# v5-IRarray.net
KiCad netlist of a schematic drawn in Altium Designer
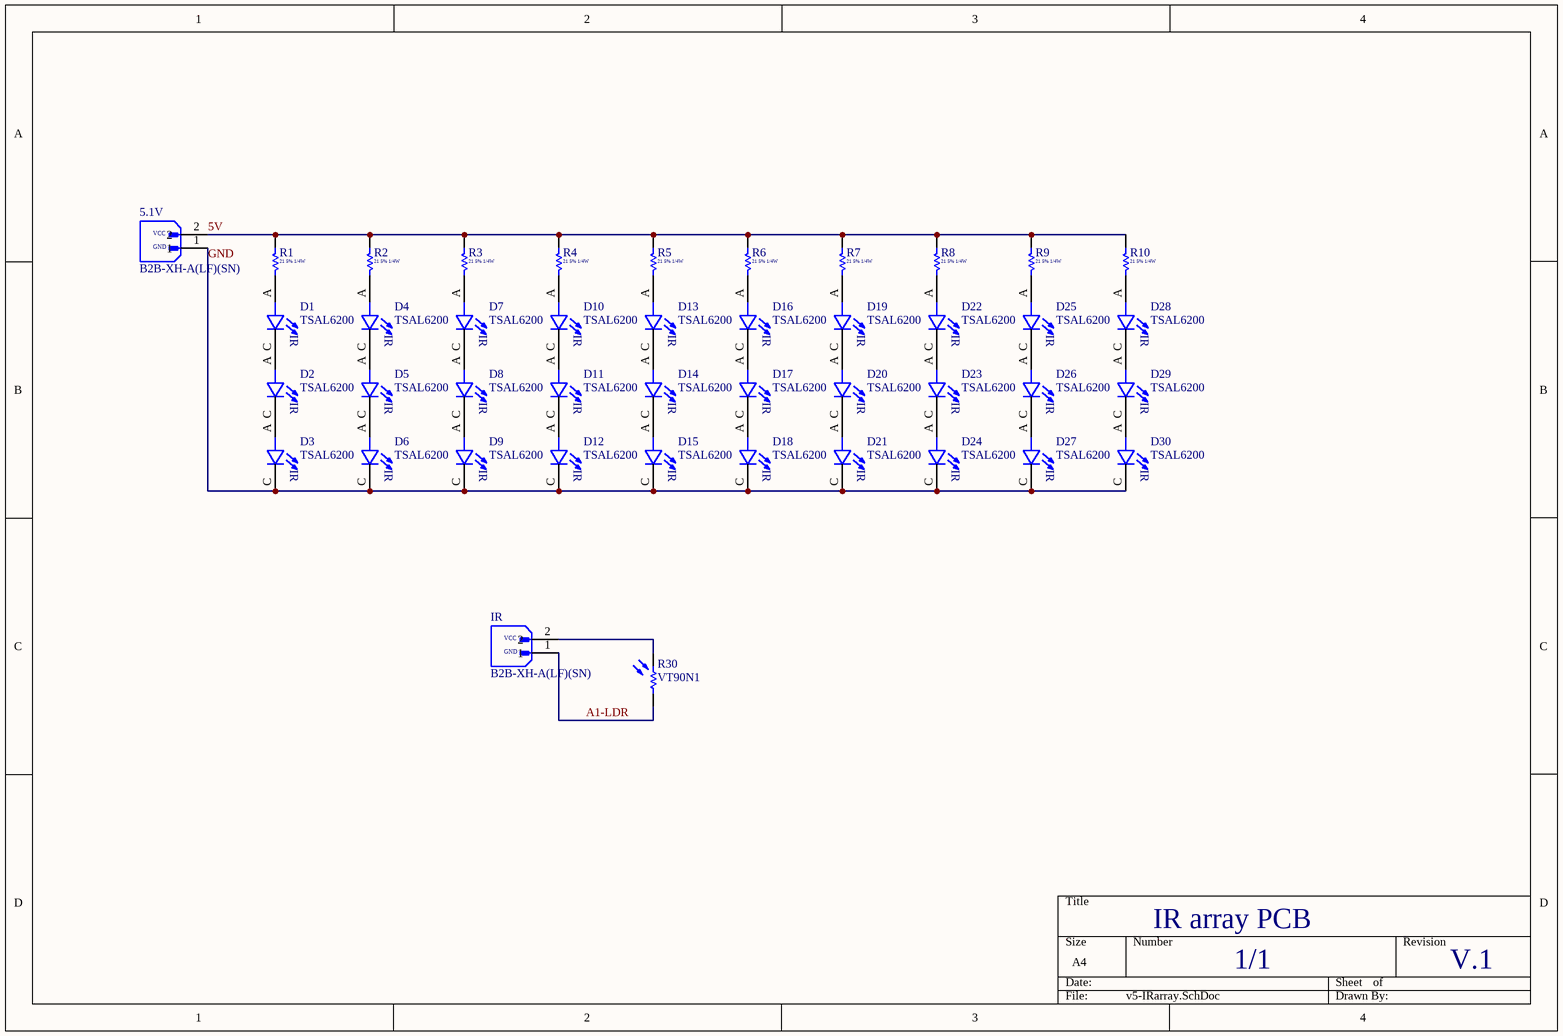
[diagram p0: v5-IRarray.SchDoc]

(export (version "E")
  (design (tool "Eeschema 10.0.6"))
  (components
    (comp (ref "5.1V")
      (value "B2B-XH-A(LF)(SN)")
      (footprint "JST_B2B-XH-A(LF)(SN)")
      (description "Connector Header Through Hole 2 position 0.098 (2.50mm)")
      (fields (field (name "MF") "JST Sales America Inc."))
      (libsource (lib "B2B-XH-A(LF)(SN)") (part "B2B-XH-A(LF)(SN)"))
    )
    (comp (ref "D1")
      (value "TSAL6200")
      (footprint "SFH45547")
      (libsource (lib "IRarrayPCB") (part "SFH4547"))
    )
    (comp (ref "D2")
      (value "TSAL6200")
      (footprint "SFH45547")
      (libsource (lib "IRarrayPCB") (part "SFH4547"))
    )
    (comp (ref "D3")
      (value "TSAL6200")
      (footprint "SFH45547")
      (libsource (lib "IRarrayPCB") (part "SFH4547"))
    )
    (comp (ref "D4")
      (value "TSAL6200")
      (footprint "SFH45547")
      (libsource (lib "IRarrayPCB") (part "SFH4547"))
    )
    (comp (ref "D5")
      (value "TSAL6200")
      (footprint "SFH45547")
      (libsource (lib "IRarrayPCB") (part "SFH4547"))
    )
    (comp (ref "D6")
      (value "TSAL6200")
      (footprint "SFH45547")
      (libsource (lib "IRarrayPCB") (part "SFH4547"))
    )
    (comp (ref "D7")
      (value "TSAL6200")
      (footprint "SFH45547")
      (libsource (lib "IRarrayPCB") (part "SFH4547"))
    )
    (comp (ref "D8")
      (value "TSAL6200")
      (footprint "SFH45547")
      (libsource (lib "IRarrayPCB") (part "SFH4547"))
    )
    (comp (ref "D9")
      (value "TSAL6200")
      (footprint "SFH45547")
      (libsource (lib "IRarrayPCB") (part "SFH4547"))
    )
    (comp (ref "D10")
      (value "TSAL6200")
      (footprint "SFH45547")
      (libsource (lib "IRarrayPCB") (part "SFH4547"))
    )
    (comp (ref "D11")
      (value "TSAL6200")
      (footprint "SFH45547")
      (libsource (lib "IRarrayPCB") (part "SFH4547"))
    )
    (comp (ref "D12")
      (value "TSAL6200")
      (footprint "SFH45547")
      (libsource (lib "IRarrayPCB") (part "SFH4547"))
    )
    (comp (ref "D13")
      (value "TSAL6200")
      (footprint "SFH45547")
      (libsource (lib "IRarrayPCB") (part "SFH4547"))
    )
    (comp (ref "D14")
      (value "TSAL6200")
      (footprint "SFH45547")
      (libsource (lib "IRarrayPCB") (part "SFH4547"))
    )
    (comp (ref "D15")
      (value "TSAL6200")
      (footprint "SFH45547")
      (libsource (lib "IRarrayPCB") (part "SFH4547"))
    )
    (comp (ref "D16")
      (value "TSAL6200")
      (footprint "SFH45547")
      (libsource (lib "IRarrayPCB") (part "SFH4547"))
    )
    (comp (ref "D17")
      (value "TSAL6200")
      (footprint "SFH45547")
      (libsource (lib "IRarrayPCB") (part "SFH4547"))
    )
    (comp (ref "D18")
      (value "TSAL6200")
      (footprint "SFH45547")
      (libsource (lib "IRarrayPCB") (part "SFH4547"))
    )
    (comp (ref "D19")
      (value "TSAL6200")
      (footprint "SFH45547")
      (libsource (lib "IRarrayPCB") (part "SFH4547"))
    )
    (comp (ref "D20")
      (value "TSAL6200")
      (footprint "SFH45547")
      (libsource (lib "IRarrayPCB") (part "SFH4547"))
    )
    (comp (ref "D21")
      (value "TSAL6200")
      (footprint "SFH45547")
      (libsource (lib "IRarrayPCB") (part "SFH4547"))
    )
    (comp (ref "D22")
      (value "TSAL6200")
      (footprint "SFH45547")
      (libsource (lib "IRarrayPCB") (part "SFH4547"))
    )
    (comp (ref "D23")
      (value "TSAL6200")
      (footprint "SFH45547")
      (libsource (lib "IRarrayPCB") (part "SFH4547"))
    )
    (comp (ref "D24")
      (value "TSAL6200")
      (footprint "SFH45547")
      (libsource (lib "IRarrayPCB") (part "SFH4547"))
    )
    (comp (ref "D25")
      (value "TSAL6200")
      (footprint "SFH45547")
      (libsource (lib "IRarrayPCB") (part "SFH4547"))
    )
    (comp (ref "D26")
      (value "TSAL6200")
      (footprint "SFH45547")
      (libsource (lib "IRarrayPCB") (part "SFH4547"))
    )
    (comp (ref "D27")
      (value "TSAL6200")
      (footprint "SFH45547")
      (libsource (lib "IRarrayPCB") (part "SFH4547"))
    )
    (comp (ref "D28")
      (value "TSAL6200")
      (footprint "SFH45547")
      (libsource (lib "IRarrayPCB") (part "SFH4547"))
    )
    (comp (ref "D29")
      (value "TSAL6200")
      (footprint "SFH45547")
      (libsource (lib "IRarrayPCB") (part "SFH4547"))
    )
    (comp (ref "D30")
      (value "TSAL6200")
      (footprint "SFH45547")
      (libsource (lib "IRarrayPCB") (part "SFH4547"))
    )
    (comp (ref "IR")
      (value "B2B-XH-A(LF)(SN)")
      (footprint "JST_B2B-XH-A(LF)(SN)")
      (description "Connector Header Through Hole 2 position 0.098 (2.50mm)")
      (fields (field (name "MF") "JST Sales America Inc."))
      (libsource (lib "B2B-XH-A(LF)(SN)") (part "B2B-XH-A(LF)(SN)"))
    )
    (comp (ref "R1")
      (value "21 5% 1/4W")
      (footprint "R1206")
      (description "SMD 1206 0.25W 5% 200V")
      (libsource (lib "MyLib1") (part "R-1206"))
    )
    (comp (ref "R2")
      (value "21 5% 1/4W")
      (footprint "R1206")
      (description "SMD 1206 0.25W 5% 200V")
      (libsource (lib "MyLib1") (part "R-1206"))
    )
    (comp (ref "R3")
      (value "21 5% 1/4W")
      (footprint "R1206")
      (description "SMD 1206 0.25W 5% 200V")
      (libsource (lib "MyLib1") (part "R-1206"))
    )
    (comp (ref "R4")
      (value "21 5% 1/4W")
      (footprint "R1206")
      (description "SMD 1206 0.25W 5% 200V")
      (libsource (lib "MyLib1") (part "R-1206"))
    )
    (comp (ref "R5")
      (value "21 5% 1/4W")
      (footprint "R1206")
      (description "SMD 1206 0.25W 5% 200V")
      (libsource (lib "MyLib1") (part "R-1206"))
    )
    (comp (ref "R6")
      (value "21 5% 1/4W")
      (footprint "R1206")
      (description "SMD 1206 0.25W 5% 200V")
      (libsource (lib "MyLib1") (part "R-1206"))
    )
    (comp (ref "R7")
      (value "21 5% 1/4W")
      (footprint "R1206")
      (description "SMD 1206 0.25W 5% 200V")
      (libsource (lib "MyLib1") (part "R-1206"))
    )
    (comp (ref "R8")
      (value "21 5% 1/4W")
      (footprint "R1206")
      (description "SMD 1206 0.25W 5% 200V")
      (libsource (lib "MyLib1") (part "R-1206"))
    )
    (comp (ref "R9")
      (value "21 5% 1/4W")
      (footprint "R1206")
      (description "SMD 1206 0.25W 5% 200V")
      (libsource (lib "MyLib1") (part "R-1206"))
    )
    (comp (ref "R10")
      (value "21 5% 1/4W")
      (footprint "R1206")
      (description "SMD 1206 0.25W 5% 200V")
      (libsource (lib "MyLib1") (part "R-1206"))
    )
    (comp (ref "R30")
      (value "VT90N1")
      (footprint "EXCE-VT90N1")
      (description "Photoconductive Resistor, 200 kOhm, 100 V, 80 mW, -40 to 75 degC, 2-Pin THD, RoHS")
      (fields (field (name "MANUFACTURER") "Excelitas Technology"))
      (libsource (lib "Altium Content Vault") (part "PHOTO-RES-2"))
    )
  )
  (nets
    (net (code "1") (name "/5V") (class "Default")
      (node (ref "5.1V") (pin "2") (pinfunction "2_2") (pintype "passive"))
      (node (ref "R1") (pin "1") (pinfunction "1_1") (pintype "passive"))
      (node (ref "R10") (pin "1") (pinfunction "1_1") (pintype "passive"))
      (node (ref "R2") (pin "1") (pinfunction "1_1") (pintype "passive"))
      (node (ref "R3") (pin "1") (pinfunction "1_1") (pintype "passive"))
      (node (ref "R4") (pin "1") (pinfunction "1_1") (pintype "passive"))
      (node (ref "R5") (pin "1") (pinfunction "1_1") (pintype "passive"))
      (node (ref "R6") (pin "1") (pinfunction "1_1") (pintype "passive"))
      (node (ref "R7") (pin "1") (pinfunction "1_1") (pintype "passive"))
      (node (ref "R8") (pin "1") (pinfunction "1_1") (pintype "passive"))
      (node (ref "R9") (pin "1") (pinfunction "1_1") (pintype "passive"))
    )
    (net (code "2") (name "/A1-LDR") (class "Default")
      (node (ref "IR") (pin "1") (pinfunction "1_1") (pintype "passive"))
      (node (ref "R30") (pin "1") (pinfunction "1_1") (pintype "passive"))
    )
    (net (code "3") (name "/GND") (class "Default")
      (node (ref "5.1V") (pin "1") (pinfunction "1_1") (pintype "passive"))
      (node (ref "D12") (pin "C") (pinfunction "C_C") (pintype "passive"))
      (node (ref "D15") (pin "C") (pinfunction "C_C") (pintype "passive"))
      (node (ref "D18") (pin "C") (pinfunction "C_C") (pintype "passive"))
      (node (ref "D21") (pin "C") (pinfunction "C_C") (pintype "passive"))
      (node (ref "D24") (pin "C") (pinfunction "C_C") (pintype "passive"))
      (node (ref "D27") (pin "C") (pinfunction "C_C") (pintype "passive"))
      (node (ref "D3") (pin "C") (pinfunction "C_C") (pintype "passive"))
      (node (ref "D30") (pin "C") (pinfunction "C_C") (pintype "passive"))
      (node (ref "D6") (pin "C") (pinfunction "C_C") (pintype "passive"))
      (node (ref "D9") (pin "C") (pinfunction "C_C") (pintype "passive"))
    )
    (net (code "4") (name "Net-(D1-PadA)") (class "Default")
      (node (ref "D1") (pin "A") (pinfunction "A_A") (pintype "passive"))
      (node (ref "R1") (pin "2") (pinfunction "2_2") (pintype "passive"))
    )
    (net (code "5") (name "Net-(D1-PadC)") (class "Default")
      (node (ref "D1") (pin "C") (pinfunction "C_C") (pintype "passive"))
      (node (ref "D2") (pin "A") (pinfunction "A_A") (pintype "passive"))
    )
    (net (code "6") (name "Net-(D2-PadC)") (class "Default")
      (node (ref "D2") (pin "C") (pinfunction "C_C") (pintype "passive"))
      (node (ref "D3") (pin "A") (pinfunction "A_A") (pintype "passive"))
    )
    (net (code "7") (name "Net-(D4-PadA)") (class "Default")
      (node (ref "D4") (pin "A") (pinfunction "A_A") (pintype "passive"))
      (node (ref "R2") (pin "2") (pinfunction "2_2") (pintype "passive"))
    )
    (net (code "8") (name "Net-(D4-PadC)") (class "Default")
      (node (ref "D4") (pin "C") (pinfunction "C_C") (pintype "passive"))
      (node (ref "D5") (pin "A") (pinfunction "A_A") (pintype "passive"))
    )
    (net (code "9") (name "Net-(D5-PadC)") (class "Default")
      (node (ref "D5") (pin "C") (pinfunction "C_C") (pintype "passive"))
      (node (ref "D6") (pin "A") (pinfunction "A_A") (pintype "passive"))
    )
    (net (code "10") (name "Net-(D7-PadA)") (class "Default")
      (node (ref "D7") (pin "A") (pinfunction "A_A") (pintype "passive"))
      (node (ref "R3") (pin "2") (pinfunction "2_2") (pintype "passive"))
    )
    (net (code "11") (name "Net-(D7-PadC)") (class "Default")
      (node (ref "D7") (pin "C") (pinfunction "C_C") (pintype "passive"))
      (node (ref "D8") (pin "A") (pinfunction "A_A") (pintype "passive"))
    )
    (net (code "12") (name "Net-(D8-PadC)") (class "Default")
      (node (ref "D8") (pin "C") (pinfunction "C_C") (pintype "passive"))
      (node (ref "D9") (pin "A") (pinfunction "A_A") (pintype "passive"))
    )
    (net (code "13") (name "Net-(D10-PadA)") (class "Default")
      (node (ref "D10") (pin "A") (pinfunction "A_A") (pintype "passive"))
      (node (ref "R4") (pin "2") (pinfunction "2_2") (pintype "passive"))
    )
    (net (code "14") (name "Net-(D10-PadC)") (class "Default")
      (node (ref "D10") (pin "C") (pinfunction "C_C") (pintype "passive"))
      (node (ref "D11") (pin "A") (pinfunction "A_A") (pintype "passive"))
    )
    (net (code "15") (name "Net-(D11-PadC)") (class "Default")
      (node (ref "D11") (pin "C") (pinfunction "C_C") (pintype "passive"))
      (node (ref "D12") (pin "A") (pinfunction "A_A") (pintype "passive"))
    )
    (net (code "16") (name "Net-(D13-PadA)") (class "Default")
      (node (ref "D13") (pin "A") (pinfunction "A_A") (pintype "passive"))
      (node (ref "R5") (pin "2") (pinfunction "2_2") (pintype "passive"))
    )
    (net (code "17") (name "Net-(D13-PadC)") (class "Default")
      (node (ref "D13") (pin "C") (pinfunction "C_C") (pintype "passive"))
      (node (ref "D14") (pin "A") (pinfunction "A_A") (pintype "passive"))
    )
    (net (code "18") (name "Net-(D14-PadC)") (class "Default")
      (node (ref "D14") (pin "C") (pinfunction "C_C") (pintype "passive"))
      (node (ref "D15") (pin "A") (pinfunction "A_A") (pintype "passive"))
    )
    (net (code "19") (name "Net-(D16-PadA)") (class "Default")
      (node (ref "D16") (pin "A") (pinfunction "A_A") (pintype "passive"))
      (node (ref "R6") (pin "2") (pinfunction "2_2") (pintype "passive"))
    )
    (net (code "20") (name "Net-(D16-PadC)") (class "Default")
      (node (ref "D16") (pin "C") (pinfunction "C_C") (pintype "passive"))
      (node (ref "D17") (pin "A") (pinfunction "A_A") (pintype "passive"))
    )
    (net (code "21") (name "Net-(D17-PadC)") (class "Default")
      (node (ref "D17") (pin "C") (pinfunction "C_C") (pintype "passive"))
      (node (ref "D18") (pin "A") (pinfunction "A_A") (pintype "passive"))
    )
    (net (code "22") (name "Net-(D19-PadA)") (class "Default")
      (node (ref "D19") (pin "A") (pinfunction "A_A") (pintype "passive"))
      (node (ref "R7") (pin "2") (pinfunction "2_2") (pintype "passive"))
    )
    (net (code "23") (name "Net-(D19-PadC)") (class "Default")
      (node (ref "D19") (pin "C") (pinfunction "C_C") (pintype "passive"))
      (node (ref "D20") (pin "A") (pinfunction "A_A") (pintype "passive"))
    )
    (net (code "24") (name "Net-(D20-PadC)") (class "Default")
      (node (ref "D20") (pin "C") (pinfunction "C_C") (pintype "passive"))
      (node (ref "D21") (pin "A") (pinfunction "A_A") (pintype "passive"))
    )
    (net (code "25") (name "Net-(D22-PadA)") (class "Default")
      (node (ref "D22") (pin "A") (pinfunction "A_A") (pintype "passive"))
      (node (ref "R8") (pin "2") (pinfunction "2_2") (pintype "passive"))
    )
    (net (code "26") (name "Net-(D22-PadC)") (class "Default")
      (node (ref "D22") (pin "C") (pinfunction "C_C") (pintype "passive"))
      (node (ref "D23") (pin "A") (pinfunction "A_A") (pintype "passive"))
    )
    (net (code "27") (name "Net-(D23-PadC)") (class "Default")
      (node (ref "D23") (pin "C") (pinfunction "C_C") (pintype "passive"))
      (node (ref "D24") (pin "A") (pinfunction "A_A") (pintype "passive"))
    )
    (net (code "28") (name "Net-(D25-PadA)") (class "Default")
      (node (ref "D25") (pin "A") (pinfunction "A_A") (pintype "passive"))
      (node (ref "R9") (pin "2") (pinfunction "2_2") (pintype "passive"))
    )
    (net (code "29") (name "Net-(D25-PadC)") (class "Default")
      (node (ref "D25") (pin "C") (pinfunction "C_C") (pintype "passive"))
      (node (ref "D26") (pin "A") (pinfunction "A_A") (pintype "passive"))
    )
    (net (code "30") (name "Net-(D26-PadC)") (class "Default")
      (node (ref "D26") (pin "C") (pinfunction "C_C") (pintype "passive"))
      (node (ref "D27") (pin "A") (pinfunction "A_A") (pintype "passive"))
    )
    (net (code "31") (name "Net-(D28-PadA)") (class "Default")
      (node (ref "D28") (pin "A") (pinfunction "A_A") (pintype "passive"))
      (node (ref "R10") (pin "2") (pinfunction "2_2") (pintype "passive"))
    )
    (net (code "32") (name "Net-(D28-PadC)") (class "Default")
      (node (ref "D28") (pin "C") (pinfunction "C_C") (pintype "passive"))
      (node (ref "D29") (pin "A") (pinfunction "A_A") (pintype "passive"))
    )
    (net (code "33") (name "Net-(D29-PadC)") (class "Default")
      (node (ref "D29") (pin "C") (pinfunction "C_C") (pintype "passive"))
      (node (ref "D30") (pin "A") (pinfunction "A_A") (pintype "passive"))
    )
    (net (code "34") (name "Net-(IR-Pad2)") (class "Default")
      (node (ref "IR") (pin "2") (pinfunction "2_2") (pintype "passive"))
      (node (ref "R30") (pin "2") (pinfunction "2_2") (pintype "passive"))
    )
  )
)
